# Buttons.net
KiCad netlist of a schematic drawn in Altium Designer
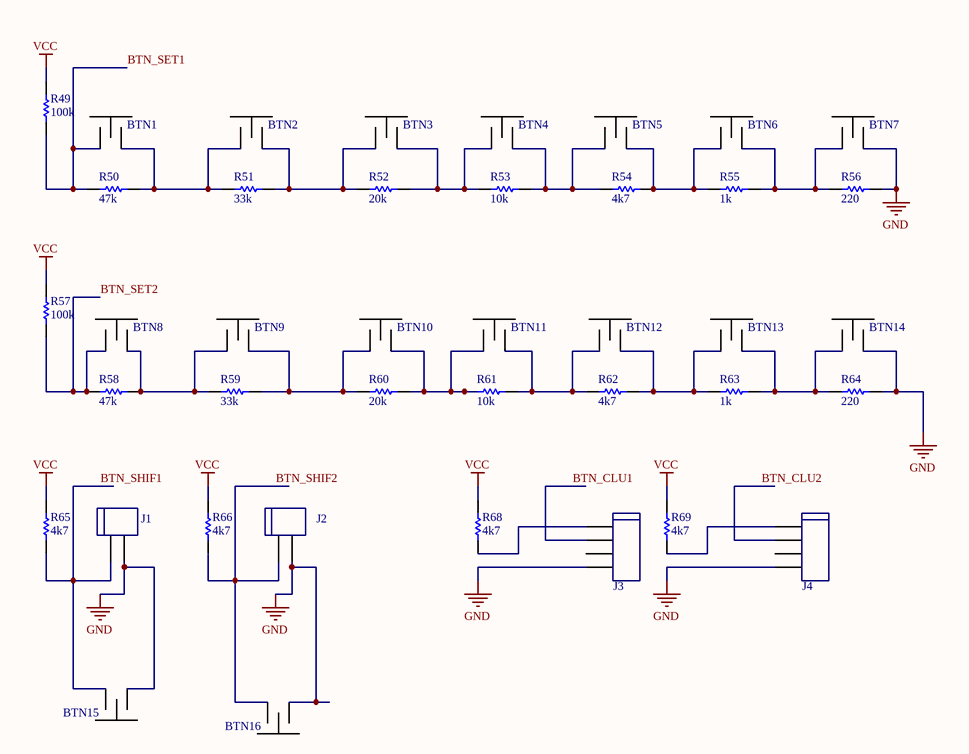
[diagram p0: Buttons.SchDoc]

(export (version "E")
  (design (tool "Eeschema 10.0.6"))
  (components
    (comp (ref "BTN1")
      (value "Push Button KAN28 1.5A")
      (footprint "KAN-28 Btn")
      (libsource (lib "LibDevs") (part "Push Button KAN28 1.5A"))
    )
    (comp (ref "BTN2")
      (value "Push Button KAN28 1.5A")
      (footprint "KAN-28 Btn")
      (libsource (lib "LibDevs") (part "Push Button KAN28 1.5A"))
    )
    (comp (ref "BTN3")
      (value "Push Button KAN28 1.5A")
      (footprint "KAN-28 Btn")
      (libsource (lib "LibDevs") (part "Push Button KAN28 1.5A"))
    )
    (comp (ref "BTN4")
      (value "Push Button KAN28 1.5A")
      (footprint "KAN-28 Btn")
      (libsource (lib "LibDevs") (part "Push Button KAN28 1.5A"))
    )
    (comp (ref "BTN5")
      (value "Push Button KAN28 1.5A")
      (footprint "KAN-28 Btn")
      (libsource (lib "LibDevs") (part "Push Button KAN28 1.5A"))
    )
    (comp (ref "BTN6")
      (value "Push Button KAN28 1.5A")
      (footprint "KAN-28 Btn")
      (libsource (lib "LibDevs") (part "Push Button KAN28 1.5A"))
    )
    (comp (ref "BTN7")
      (value "Push Button KAN28 1.5A")
      (footprint "KAN-28 Btn")
      (libsource (lib "LibDevs") (part "Push Button KAN28 1.5A"))
    )
    (comp (ref "BTN8")
      (value "Push Button KAN28 1.5A")
      (footprint "KAN-28 Btn")
      (libsource (lib "LibDevs") (part "Push Button KAN28 1.5A"))
    )
    (comp (ref "BTN9")
      (value "Push Button KAN28 1.5A")
      (footprint "KAN-28 Btn")
      (libsource (lib "LibDevs") (part "Push Button KAN28 1.5A"))
    )
    (comp (ref "BTN10")
      (value "Push Button KAN28 1.5A")
      (footprint "KAN-28 Btn")
      (libsource (lib "LibDevs") (part "Push Button KAN28 1.5A"))
    )
    (comp (ref "BTN11")
      (value "Push Button KAN28 1.5A")
      (footprint "KAN-28 Btn")
      (libsource (lib "LibDevs") (part "Push Button KAN28 1.5A"))
    )
    (comp (ref "BTN12")
      (value "Push Button KAN28 1.5A")
      (footprint "KAN-28 Btn")
      (libsource (lib "LibDevs") (part "Push Button KAN28 1.5A"))
    )
    (comp (ref "BTN13")
      (value "Push Button KAN28 1.5A")
      (footprint "KAN-28 Btn")
      (libsource (lib "LibDevs") (part "Push Button KAN28 1.5A"))
    )
    (comp (ref "BTN14")
      (value "Push Button KAN28 1.5A")
      (footprint "KAN-28 Btn")
      (libsource (lib "LibDevs") (part "Push Button KAN28 1.5A"))
    )
    (comp (ref "BTN15")
      (value "Push Button KAN28 1.5A")
      (footprint "KAN-28 Btn")
      (libsource (lib "LibDevs") (part "Push Button KAN28 1.5A"))
    )
    (comp (ref "BTN16")
      (value "Push Button KAN28 1.5A")
      (footprint "KAN-28 Btn")
      (libsource (lib "LibDevs") (part "Push Button KAN28 1.5A"))
    )
    (comp (ref "J1")
      (value "JST 2 PIN 1.25mm SMD")
      (footprint "JST 2 Pin 1.25mm")
      (libsource (lib "LibDevs") (part "JST 2 PIN 1.25mm SMD"))
    )
    (comp (ref "J2")
      (value "JST 2 PIN 1.25mm SMD")
      (footprint "JST 2 Pin 1.25mm")
      (libsource (lib "LibDevs") (part "JST 2 PIN 1.25mm SMD"))
    )
    (comp (ref "J3")
      (value "JST 4 PIN 1.25mm SMD_1")
      (footprint "JST 4 Pin 1.25mm")
      (libsource (lib "LibDevs") (part "JST 4 PIN 1.25mm SMD_1"))
    )
    (comp (ref "J4")
      (value "JST 4 PIN 1.25mm SMD_1")
      (footprint "JST 4 Pin 1.25mm")
      (libsource (lib "LibDevs") (part "JST 4 PIN 1.25mm SMD_1"))
    )
    (comp (ref "R49")
      (value "100k")
      (footprint "0603")
      (fields (field (name "Comment") "RESISTOR GENERIC"))
      (libsource (lib "LibDevs") (part "RESISTOR GENERIC"))
    )
    (comp (ref "R50")
      (value "47k")
      (footprint "0603")
      (fields (field (name "Comment") "RESISTOR GENERIC"))
      (libsource (lib "LibDevs") (part "RESISTOR GENERIC"))
    )
    (comp (ref "R51")
      (value "33k")
      (footprint "0603")
      (fields (field (name "Comment") "RESISTOR GENERIC"))
      (libsource (lib "LibDevs") (part "RESISTOR GENERIC"))
    )
    (comp (ref "R52")
      (value "20k")
      (footprint "0603")
      (fields (field (name "Comment") "RESISTOR GENERIC"))
      (libsource (lib "LibDevs") (part "RESISTOR GENERIC"))
    )
    (comp (ref "R53")
      (value "10k")
      (footprint "0603")
      (fields (field (name "Comment") "RESISTOR GENERIC"))
      (libsource (lib "LibDevs") (part "RESISTOR GENERIC"))
    )
    (comp (ref "R54")
      (value "4k7")
      (footprint "0603")
      (fields (field (name "Comment") "RESISTOR GENERIC"))
      (libsource (lib "LibDevs") (part "RESISTOR GENERIC"))
    )
    (comp (ref "R55")
      (value "1k")
      (footprint "0603")
      (fields (field (name "Comment") "RESISTOR GENERIC"))
      (libsource (lib "LibDevs") (part "RESISTOR GENERIC"))
    )
    (comp (ref "R56")
      (value "220")
      (footprint "0603")
      (fields (field (name "Comment") "RESISTOR GENERIC"))
      (libsource (lib "LibDevs") (part "RESISTOR GENERIC"))
    )
    (comp (ref "R57")
      (value "100k")
      (footprint "0603")
      (fields (field (name "Comment") "RESISTOR GENERIC"))
      (libsource (lib "LibDevs") (part "RESISTOR GENERIC"))
    )
    (comp (ref "R58")
      (value "47k")
      (footprint "0603")
      (fields (field (name "Comment") "RESISTOR GENERIC"))
      (libsource (lib "LibDevs") (part "RESISTOR GENERIC"))
    )
    (comp (ref "R59")
      (value "33k")
      (footprint "0603")
      (fields (field (name "Comment") "RESISTOR GENERIC"))
      (libsource (lib "LibDevs") (part "RESISTOR GENERIC"))
    )
    (comp (ref "R60")
      (value "20k")
      (footprint "0603")
      (fields (field (name "Comment") "RESISTOR GENERIC"))
      (libsource (lib "LibDevs") (part "RESISTOR GENERIC"))
    )
    (comp (ref "R61")
      (value "10k")
      (footprint "0603")
      (fields (field (name "Comment") "RESISTOR GENERIC"))
      (libsource (lib "LibDevs") (part "RESISTOR GENERIC"))
    )
    (comp (ref "R62")
      (value "4k7")
      (footprint "0603")
      (fields (field (name "Comment") "RESISTOR GENERIC"))
      (libsource (lib "LibDevs") (part "RESISTOR GENERIC"))
    )
    (comp (ref "R63")
      (value "1k")
      (footprint "0603")
      (fields (field (name "Comment") "RESISTOR GENERIC"))
      (libsource (lib "LibDevs") (part "RESISTOR GENERIC"))
    )
    (comp (ref "R64")
      (value "220")
      (footprint "0603")
      (fields (field (name "Comment") "RESISTOR GENERIC"))
      (libsource (lib "LibDevs") (part "RESISTOR GENERIC"))
    )
    (comp (ref "R65")
      (value "4k7")
      (footprint "0603")
      (fields (field (name "Comment") "RESISTOR GENERIC"))
      (libsource (lib "LibDevs") (part "RESISTOR GENERIC"))
    )
    (comp (ref "R66")
      (value "4k7")
      (footprint "0603")
      (fields (field (name "Comment") "RESISTOR GENERIC"))
      (libsource (lib "LibDevs") (part "RESISTOR GENERIC"))
    )
    (comp (ref "R68")
      (value "4k7")
      (footprint "0603")
      (fields (field (name "Comment") "RESISTOR GENERIC"))
      (libsource (lib "LibDevs") (part "RESISTOR GENERIC"))
    )
    (comp (ref "R69")
      (value "4k7")
      (footprint "0603")
      (fields (field (name "Comment") "RESISTOR GENERIC"))
      (libsource (lib "LibDevs") (part "RESISTOR GENERIC"))
    )
  )
  (nets
    (net (code "1") (name "/BTN_CLU1") (class "Default")
      (node (ref "J3") (pin "2") (pinfunction "2_2") (pintype "passive"))
    )
    (net (code "2") (name "/BTN_CLU2") (class "Default")
      (node (ref "J4") (pin "2") (pinfunction "2_2") (pintype "passive"))
    )
    (net (code "3") (name "/BTN_SET1") (class "Default")
      (node (ref "BTN1") (pin "1") (pinfunction "PIN1_1") (pintype "passive"))
      (node (ref "R49") (pin "1") (pinfunction "1_1") (pintype "passive"))
      (node (ref "R50") (pin "2") (pinfunction "2_2") (pintype "passive"))
    )
    (net (code "4") (name "/BTN_SET2") (class "Default")
      (node (ref "BTN8") (pin "1") (pinfunction "PIN1_1") (pintype "passive"))
      (node (ref "R57") (pin "2") (pinfunction "2_2") (pintype "passive"))
      (node (ref "R58") (pin "1") (pinfunction "1_1") (pintype "passive"))
    )
    (net (code "5") (name "/BTN_SHIF1") (class "Default")
      (node (ref "BTN15") (pin "2") (pinfunction "PIN2_2") (pintype "passive"))
      (node (ref "J1") (pin "1") (pinfunction "PIN1_1") (pintype "passive"))
      (node (ref "R65") (pin "1") (pinfunction "1_1") (pintype "passive"))
    )
    (net (code "6") (name "/BTN_SHIF2") (class "Default")
      (node (ref "BTN16") (pin "2") (pinfunction "PIN2_2") (pintype "passive"))
      (node (ref "J2") (pin "1") (pinfunction "PIN1_1") (pintype "passive"))
      (node (ref "R66") (pin "1") (pinfunction "1_1") (pintype "passive"))
    )
    (net (code "7") (name "GND") (class "Default")
      (node (ref "BTN14") (pin "2") (pinfunction "PIN2_2") (pintype "passive"))
      (node (ref "BTN15") (pin "1") (pinfunction "PIN1_1") (pintype "passive"))
      (node (ref "BTN16") (pin "1") (pinfunction "PIN1_1") (pintype "passive"))
      (node (ref "BTN7") (pin "2") (pinfunction "PIN2_2") (pintype "passive"))
      (node (ref "J1") (pin "2") (pinfunction "PIN2_2") (pintype "passive"))
      (node (ref "J2") (pin "2") (pinfunction "PIN2_2") (pintype "passive"))
      (node (ref "J3") (pin "4") (pinfunction "4_4") (pintype "passive"))
      (node (ref "J4") (pin "4") (pinfunction "4_4") (pintype "passive"))
      (node (ref "R56") (pin "1") (pinfunction "1_1") (pintype "passive"))
      (node (ref "R64") (pin "2") (pinfunction "2_2") (pintype "passive"))
    )
    (net (code "8") (name "Net-(BTN1-PIN2)") (class "Default")
      (node (ref "BTN1") (pin "2") (pinfunction "PIN2_2") (pintype "passive"))
      (node (ref "BTN2") (pin "1") (pinfunction "PIN1_1") (pintype "passive"))
      (node (ref "R50") (pin "1") (pinfunction "1_1") (pintype "passive"))
      (node (ref "R51") (pin "2") (pinfunction "2_2") (pintype "passive"))
    )
    (net (code "9") (name "Net-(BTN2-PIN2)") (class "Default")
      (node (ref "BTN2") (pin "2") (pinfunction "PIN2_2") (pintype "passive"))
      (node (ref "BTN3") (pin "1") (pinfunction "PIN1_1") (pintype "passive"))
      (node (ref "R51") (pin "1") (pinfunction "1_1") (pintype "passive"))
      (node (ref "R52") (pin "2") (pinfunction "2_2") (pintype "passive"))
    )
    (net (code "10") (name "Net-(BTN3-PIN2)") (class "Default")
      (node (ref "BTN3") (pin "2") (pinfunction "PIN2_2") (pintype "passive"))
      (node (ref "BTN4") (pin "1") (pinfunction "PIN1_1") (pintype "passive"))
      (node (ref "R52") (pin "1") (pinfunction "1_1") (pintype "passive"))
      (node (ref "R53") (pin "2") (pinfunction "2_2") (pintype "passive"))
    )
    (net (code "11") (name "Net-(BTN4-PIN2)") (class "Default")
      (node (ref "BTN4") (pin "2") (pinfunction "PIN2_2") (pintype "passive"))
      (node (ref "BTN5") (pin "1") (pinfunction "PIN1_1") (pintype "passive"))
      (node (ref "R53") (pin "1") (pinfunction "1_1") (pintype "passive"))
      (node (ref "R54") (pin "2") (pinfunction "2_2") (pintype "passive"))
    )
    (net (code "12") (name "Net-(BTN5-PIN2)") (class "Default")
      (node (ref "BTN5") (pin "2") (pinfunction "PIN2_2") (pintype "passive"))
      (node (ref "BTN6") (pin "1") (pinfunction "PIN1_1") (pintype "passive"))
      (node (ref "R54") (pin "1") (pinfunction "1_1") (pintype "passive"))
      (node (ref "R55") (pin "2") (pinfunction "2_2") (pintype "passive"))
    )
    (net (code "13") (name "Net-(BTN6-PIN2)") (class "Default")
      (node (ref "BTN6") (pin "2") (pinfunction "PIN2_2") (pintype "passive"))
      (node (ref "BTN7") (pin "1") (pinfunction "PIN1_1") (pintype "passive"))
      (node (ref "R55") (pin "1") (pinfunction "1_1") (pintype "passive"))
      (node (ref "R56") (pin "2") (pinfunction "2_2") (pintype "passive"))
    )
    (net (code "14") (name "Net-(BTN8-PIN2)") (class "Default")
      (node (ref "BTN8") (pin "2") (pinfunction "PIN2_2") (pintype "passive"))
      (node (ref "BTN9") (pin "1") (pinfunction "PIN1_1") (pintype "passive"))
      (node (ref "R58") (pin "2") (pinfunction "2_2") (pintype "passive"))
      (node (ref "R59") (pin "1") (pinfunction "1_1") (pintype "passive"))
    )
    (net (code "15") (name "Net-(BTN10-PIN1)") (class "Default")
      (node (ref "BTN10") (pin "1") (pinfunction "PIN1_1") (pintype "passive"))
      (node (ref "BTN9") (pin "2") (pinfunction "PIN2_2") (pintype "passive"))
      (node (ref "R59") (pin "2") (pinfunction "2_2") (pintype "passive"))
      (node (ref "R60") (pin "1") (pinfunction "1_1") (pintype "passive"))
    )
    (net (code "16") (name "Net-(BTN10-PIN2)") (class "Default")
      (node (ref "BTN10") (pin "2") (pinfunction "PIN2_2") (pintype "passive"))
      (node (ref "BTN11") (pin "1") (pinfunction "PIN1_1") (pintype "passive"))
      (node (ref "R60") (pin "2") (pinfunction "2_2") (pintype "passive"))
      (node (ref "R61") (pin "1") (pinfunction "1_1") (pintype "passive"))
    )
    (net (code "17") (name "Net-(BTN11-PIN2)") (class "Default")
      (node (ref "BTN11") (pin "2") (pinfunction "PIN2_2") (pintype "passive"))
      (node (ref "BTN12") (pin "1") (pinfunction "PIN1_1") (pintype "passive"))
      (node (ref "R61") (pin "2") (pinfunction "2_2") (pintype "passive"))
      (node (ref "R62") (pin "1") (pinfunction "1_1") (pintype "passive"))
    )
    (net (code "18") (name "Net-(BTN12-PIN2)") (class "Default")
      (node (ref "BTN12") (pin "2") (pinfunction "PIN2_2") (pintype "passive"))
      (node (ref "BTN13") (pin "1") (pinfunction "PIN1_1") (pintype "passive"))
      (node (ref "R62") (pin "2") (pinfunction "2_2") (pintype "passive"))
      (node (ref "R63") (pin "1") (pinfunction "1_1") (pintype "passive"))
    )
    (net (code "19") (name "Net-(BTN13-PIN2)") (class "Default")
      (node (ref "BTN13") (pin "2") (pinfunction "PIN2_2") (pintype "passive"))
      (node (ref "BTN14") (pin "1") (pinfunction "PIN1_1") (pintype "passive"))
      (node (ref "R63") (pin "2") (pinfunction "2_2") (pintype "passive"))
      (node (ref "R64") (pin "1") (pinfunction "1_1") (pintype "passive"))
    )
    (net (code "20") (name "Net-(J3-Pad1)") (class "Default")
      (node (ref "J3") (pin "1") (pinfunction "1_1") (pintype "passive"))
      (node (ref "R68") (pin "1") (pinfunction "1_1") (pintype "passive"))
    )
    (net (code "21") (name "Net-(J4-Pad1)") (class "Default")
      (node (ref "J4") (pin "1") (pinfunction "1_1") (pintype "passive"))
      (node (ref "R69") (pin "1") (pinfunction "1_1") (pintype "passive"))
    )
    (net (code "22") (name "VCC") (class "Default")
      (node (ref "R49") (pin "2") (pinfunction "2_2") (pintype "passive"))
      (node (ref "R57") (pin "1") (pinfunction "1_1") (pintype "passive"))
      (node (ref "R65") (pin "2") (pinfunction "2_2") (pintype "passive"))
      (node (ref "R66") (pin "2") (pinfunction "2_2") (pintype "passive"))
      (node (ref "R68") (pin "2") (pinfunction "2_2") (pintype "passive"))
      (node (ref "R69") (pin "2") (pinfunction "2_2") (pintype "passive"))
    )
    (net (code "23") (name "unconnected-(J3-Pad3)") (class "Default")
      (node (ref "J3") (pin "3") (pinfunction "3_3") (pintype "passive"))
    )
    (net (code "24") (name "unconnected-(J4-Pad3)") (class "Default")
      (node (ref "J4") (pin "3") (pinfunction "3_3") (pintype "passive"))
    )
  )
)
